# ice40.net
KiCad netlist of a schematic drawn in Altium Designer
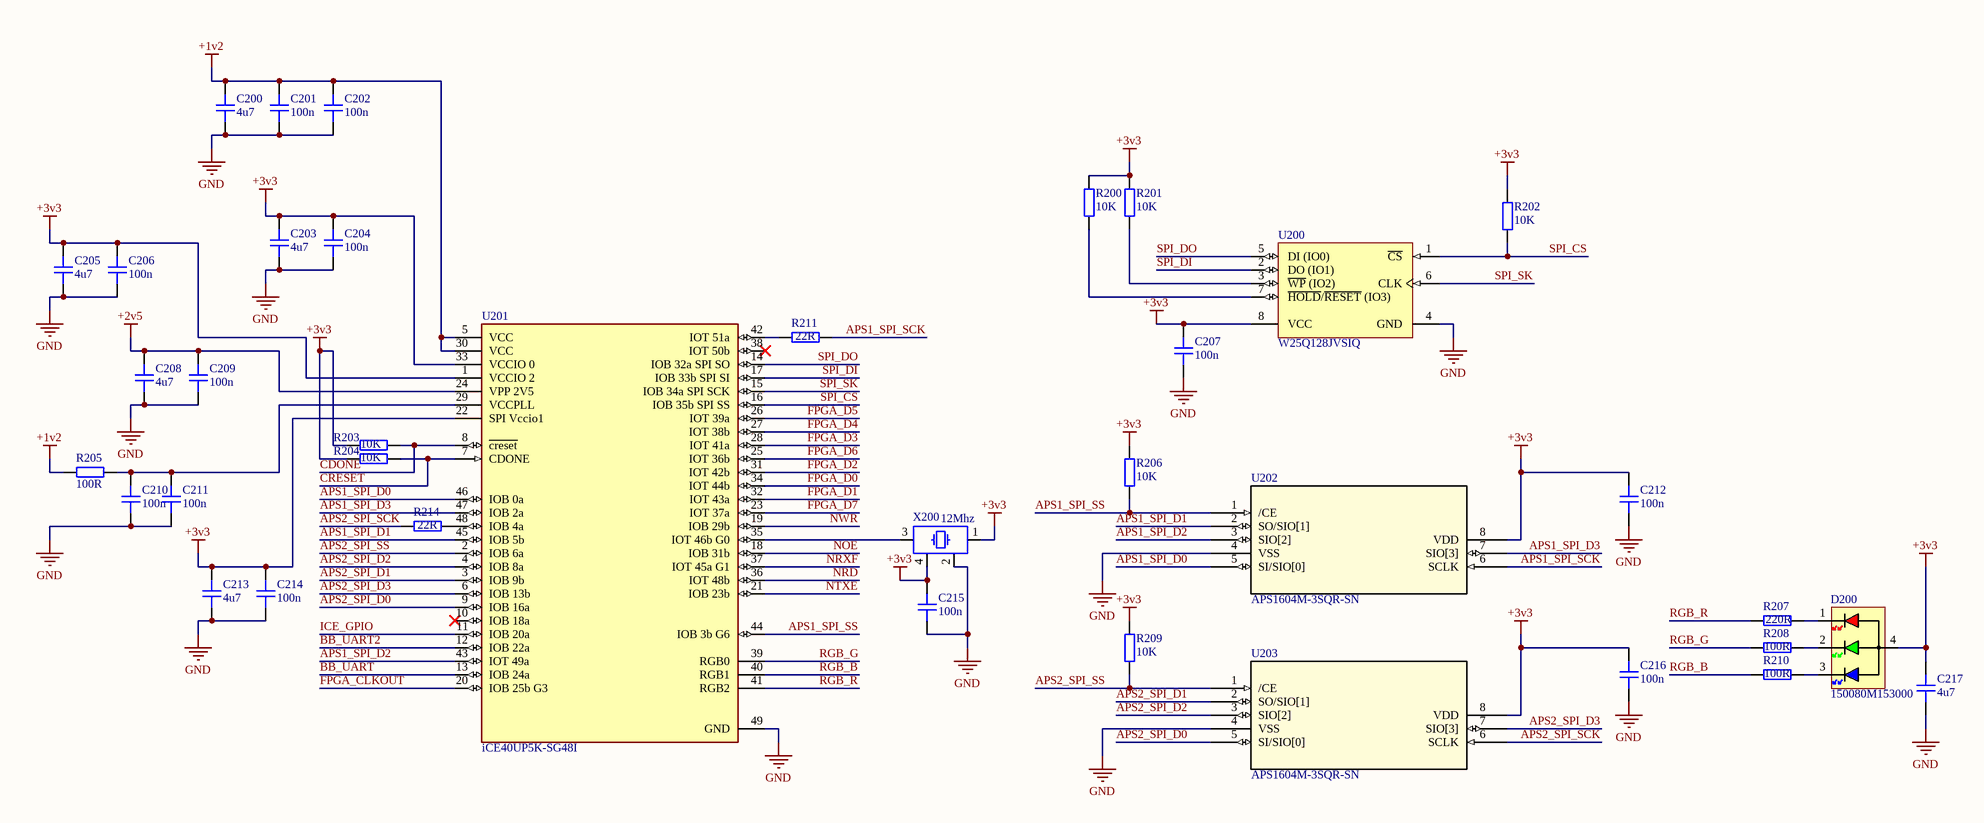
[diagram p0: ice40.SchDoc]

(export (version "E")
  (design (tool "Eeschema 10.0.6"))
  (components
    (comp (ref "C200")
      (value "4u7")
      (footprint "CAP_0402")
      (description "Capacitor SMD 0402")
      (fields (field (name "MANUFACTURER PART NUMBER") "GRM155R61E475ME15D"))
      (libsource (lib "Schematic-Lib-PhilsLab") (part "CAP_0402"))
    )
    (comp (ref "C201")
      (value "100n")
      (footprint "CAP_0402")
      (description "Capacitor SMD 0402")
      (fields (field (name "MANUFACTURER PART NUMBER") "CL05B104KO5NNNC"))
      (libsource (lib "Schematic-Lib-PhilsLab") (part "CAP_0402"))
    )
    (comp (ref "C202")
      (value "100n")
      (footprint "CAP_0402")
      (description "Capacitor SMD 0402")
      (fields (field (name "MANUFACTURER PART NUMBER") "CL05B104KO5NNNC"))
      (libsource (lib "Schematic-Lib-PhilsLab") (part "CAP_0402"))
    )
    (comp (ref "C203")
      (value "4u7")
      (footprint "CAP_0402")
      (description "Capacitor SMD 0402")
      (fields (field (name "MANUFACTURER PART NUMBER") "GRM155R61E475ME15D"))
      (libsource (lib "Schematic-Lib-PhilsLab") (part "CAP_0402"))
    )
    (comp (ref "C204")
      (value "100n")
      (footprint "CAP_0402")
      (description "Capacitor SMD 0402")
      (fields (field (name "MANUFACTURER PART NUMBER") "CL05B104KO5NNNC"))
      (libsource (lib "Schematic-Lib-PhilsLab") (part "CAP_0402"))
    )
    (comp (ref "C205")
      (value "4u7")
      (footprint "CAP_0402")
      (description "Capacitor SMD 0402")
      (fields (field (name "MANUFACTURER PART NUMBER") "GRM155R61E475ME15D"))
      (libsource (lib "Schematic-Lib-PhilsLab") (part "CAP_0402"))
    )
    (comp (ref "C206")
      (value "100n")
      (footprint "CAP_0402")
      (description "Capacitor SMD 0402")
      (fields (field (name "MANUFACTURER PART NUMBER") "CL05B104KO5NNNC"))
      (libsource (lib "Schematic-Lib-PhilsLab") (part "CAP_0402"))
    )
    (comp (ref "C207")
      (value "100n")
      (footprint "CAP_0402")
      (description "Capacitor SMD 0402")
      (fields (field (name "MANUFACTURER PART NUMBER") "CL05B104KO5NNNC"))
      (libsource (lib "Schematic-Lib-PhilsLab") (part "CAP_0402"))
    )
    (comp (ref "C208")
      (value "4u7")
      (footprint "CAP_0402")
      (description "Capacitor SMD 0402")
      (fields (field (name "MANUFACTURER PART NUMBER") "GRM155R61E475ME15D"))
      (libsource (lib "Schematic-Lib-PhilsLab") (part "CAP_0402"))
    )
    (comp (ref "C209")
      (value "100n")
      (footprint "CAP_0402")
      (description "Capacitor SMD 0402")
      (fields (field (name "MANUFACTURER PART NUMBER") "CL05B104KO5NNNC"))
      (libsource (lib "Schematic-Lib-PhilsLab") (part "CAP_0402"))
    )
    (comp (ref "C210")
      (value "100n")
      (footprint "CAP_0402")
      (description "Capacitor SMD 0402")
      (fields (field (name "MANUFACTURER PART NUMBER") "CL05B104KO5NNNC"))
      (libsource (lib "Schematic-Lib-PhilsLab") (part "CAP_0402"))
    )
    (comp (ref "C211")
      (value "100n")
      (footprint "CAP_0402")
      (description "Capacitor SMD 0402")
      (fields (field (name "MANUFACTURER PART NUMBER") "CL05B104KO5NNNC"))
      (libsource (lib "Schematic-Lib-PhilsLab") (part "CAP_0402"))
    )
    (comp (ref "C212")
      (value "100n")
      (footprint "CAP_0402")
      (description "Capacitor SMD 0402")
      (fields (field (name "MANUFACTURER PART NUMBER") "CL05B104KO5NNNC"))
      (libsource (lib "Schematic-Lib-PhilsLab") (part "CAP_0402"))
    )
    (comp (ref "C213")
      (value "4u7")
      (footprint "CAP_0402")
      (description "Capacitor SMD 0402")
      (fields (field (name "MANUFACTURER PART NUMBER") "GRM155R61E475ME15D"))
      (libsource (lib "Schematic-Lib-PhilsLab") (part "CAP_0402"))
    )
    (comp (ref "C214")
      (value "100n")
      (footprint "CAP_0402")
      (description "Capacitor SMD 0402")
      (fields (field (name "MANUFACTURER PART NUMBER") "CL05B104KO5NNNC"))
      (libsource (lib "Schematic-Lib-PhilsLab") (part "CAP_0402"))
    )
    (comp (ref "C215")
      (value "100n")
      (footprint "CAP_0402")
      (description "Capacitor SMD 0402")
      (fields (field (name "MANUFACTURER PART NUMBER") "CL05B104KO5NNNC"))
      (libsource (lib "Schematic-Lib-PhilsLab") (part "CAP_0402"))
    )
    (comp (ref "C216")
      (value "100n")
      (footprint "CAP_0402")
      (description "Capacitor SMD 0402")
      (fields (field (name "MANUFACTURER PART NUMBER") "CL05B104KO5NNNC"))
      (libsource (lib "Schematic-Lib-PhilsLab") (part "CAP_0402"))
    )
    (comp (ref "C217")
      (value "4u7")
      (footprint "CAP_0402")
      (description "Capacitor SMD 0402")
      (fields (field (name "MANUFACTURER PART NUMBER") "GRM155R61E475ME15D"))
      (libsource (lib "Schematic-Lib-PhilsLab") (part "CAP_0402"))
    )
    (comp (ref "D200")
      (value "150080M153000")
      (footprint "150080M153000")
      (description "RGB LED Common Anode SMD Diffused 0805 Top View")
      (fields (field (name "MANUFACTURER") "Wurth"))
      (libsource (lib "Schematic-Lib-PhilsLab") (part "150080M153000"))
    )
    (comp (ref "R200")
      (value "10K")
      (footprint "RES_0402")
      (description "Resistor SMD 0402")
      (fields (field (name "MANUFACTURER PART NUMBER") "0402WGF1002TCE"))
      (libsource (lib "Schematic-Lib-PhilsLab") (part "RES_0402"))
    )
    (comp (ref "R201")
      (value "10K")
      (footprint "RES_0402")
      (description "Resistor SMD 0402")
      (fields (field (name "MANUFACTURER PART NUMBER") "0402WGF1002TCE"))
      (libsource (lib "Schematic-Lib-PhilsLab") (part "RES_0402"))
    )
    (comp (ref "R202")
      (value "10K")
      (footprint "RES_0402")
      (description "Resistor SMD 0402")
      (fields (field (name "MANUFACTURER PART NUMBER") "0402WGF1002TCE"))
      (libsource (lib "Schematic-Lib-PhilsLab") (part "RES_0402"))
    )
    (comp (ref "R203")
      (value "10K")
      (footprint "RES_0402")
      (description "Resistor SMD 0402")
      (fields (field (name "MANUFACTURER PART NUMBER") "0402WGF1002TCE"))
      (libsource (lib "Schematic-Lib-PhilsLab") (part "RES_0402"))
    )
    (comp (ref "R204")
      (value "10K")
      (footprint "RES_0402")
      (description "Resistor SMD 0402")
      (fields (field (name "MANUFACTURER PART NUMBER") "0402WGF1002TCE"))
      (libsource (lib "Schematic-Lib-PhilsLab") (part "RES_0402"))
    )
    (comp (ref "R205")
      (value "100R")
      (footprint "RES_0402")
      (description "Resistor SMD 0402")
      (fields (field (name "MANUFACTURER PART NUMBER") "0402WGF1000TCE"))
      (libsource (lib "Schematic-Lib-PhilsLab") (part "RES_0402"))
    )
    (comp (ref "R206")
      (value "10K")
      (footprint "RES_0402")
      (description "Resistor SMD 0402")
      (fields (field (name "MANUFACTURER PART NUMBER") "0402WGF1002TCE"))
      (libsource (lib "Schematic-Lib-PhilsLab") (part "RES_0402"))
    )
    (comp (ref "R207")
      (value "220R")
      (footprint "RES_0402")
      (description "Resistor SMD 0402")
      (fields (field (name "MANUFACTURER PART NUMBER") "0402WGF2200TCE"))
      (libsource (lib "Schematic-Lib-PhilsLab") (part "RES_0402"))
    )
    (comp (ref "R208")
      (value "100R")
      (footprint "RES_0402")
      (description "Resistor SMD 0402")
      (fields (field (name "MANUFACTURER PART NUMBER") "0402WGF1000TCE"))
      (libsource (lib "Schematic-Lib-PhilsLab") (part "RES_0402"))
    )
    (comp (ref "R209")
      (value "10K")
      (footprint "RES_0402")
      (description "Resistor SMD 0402")
      (fields (field (name "MANUFACTURER PART NUMBER") "0402WGF1002TCE"))
      (libsource (lib "Schematic-Lib-PhilsLab") (part "RES_0402"))
    )
    (comp (ref "R210")
      (value "100R")
      (footprint "RES_0402")
      (description "Resistor SMD 0402")
      (fields (field (name "MANUFACTURER PART NUMBER") "0402WGF1000TCE"))
      (libsource (lib "Schematic-Lib-PhilsLab") (part "RES_0402"))
    )
    (comp (ref "R211")
      (value "22R")
      (footprint "RES_0402")
      (description "Resistor SMD 0402")
      (fields (field (name "MANUFACTURER PART NUMBER") "0402WGF220JTCE"))
      (libsource (lib "Schematic-Lib-PhilsLab") (part "RES_0402"))
    )
    (comp (ref "R214")
      (value "22R")
      (footprint "RES_0402")
      (description "Resistor SMD 0402")
      (fields (field (name "MANUFACTURER PART NUMBER") "0402WGF220JTCE"))
      (libsource (lib "Schematic-Lib-PhilsLab") (part "RES_0402"))
    )
    (comp (ref "U200")
      (value "W25Q128JVSIQ")
      (footprint "WINB-SOIC-8_M")
      (fields (field (name "MANUFACTURER") "Winbond"))
      (libsource (lib "Altium Content Vault") (part "WINB-W25Q128FVSIG-SOIC-8"))
    )
    (comp (ref "U201")
      (value "iCE40UP5K-SG48I")
      (footprint "FP-QFN-48-IPC_C")
      (description "ICE40-ULTRAPLUS, 5280 LUTS, 1.2V")
      (fields
        (field (name "MANUFACTURER") "Lattice")
        (field (name "OCTOPART") "https://octopart.com/ice40up5k-sg48i-lattice+semiconductor-87369311")
      )
      (libsource (lib "Altium Content Vault") (part "90c839ece6b9b86f6dd6a74a4566a88"))
    )
    (comp (ref "U202")
      (value "APS1604M-3SQR-SN")
      (footprint "SOP8L_APS1604M-3SQR-SN_APY")
      (description "No Description Available")
      (libsource (lib "APS1604M-3SQR-SN") (part "APS1604M-3SQR-SN"))
    )
    (comp (ref "U203")
      (value "APS1604M-3SQR-SN")
      (footprint "SOP8L_APS1604M-3SQR-SN_APY")
      (description "No Description Available")
      (libsource (lib "APS1604M-3SQR-SN") (part "APS1604M-3SQR-SN"))
    )
    (comp (ref "X200")
      (value "12Mhz")
      (footprint "XTAL_2520")
      (description "Crystal SMD 2520")
      (fields (field (name "MANUFACTURER PART NUMBER") "SX2M12.000B10F20TNN"))
      (libsource (lib "Schematic-Lib-PhilsLab") (part "XTAL_2520"))
    )
  )
  (nets
    (net (code "1") (name "+1v2") (class "Default")
      (node (ref "C200") (pin "2") (pinfunction "2_2") (pintype "passive"))
      (node (ref "C201") (pin "2") (pinfunction "2_2") (pintype "passive"))
      (node (ref "C202") (pin "2") (pinfunction "2_2") (pintype "passive"))
      (node (ref "R205") (pin "1") (pinfunction "1_1") (pintype "passive"))
      (node (ref "U201") (pin "30") (pinfunction "VCC_30") (pintype "power_in"))
      (node (ref "U201") (pin "5") (pinfunction "VCC_5") (pintype "power_in"))
    )
    (net (code "2") (name "+2v5") (class "Default")
      (node (ref "C208") (pin "2") (pinfunction "2_2") (pintype "passive"))
      (node (ref "C209") (pin "2") (pinfunction "2_2") (pintype "passive"))
      (node (ref "U201") (pin "24") (pinfunction "VPP_2V5_24") (pintype "power_in"))
    )
    (net (code "3") (name "+3v3") (class "Default")
      (node (ref "C203") (pin "2") (pinfunction "2_2") (pintype "passive"))
      (node (ref "C204") (pin "2") (pinfunction "2_2") (pintype "passive"))
      (node (ref "C205") (pin "2") (pinfunction "2_2") (pintype "passive"))
      (node (ref "C206") (pin "2") (pinfunction "2_2") (pintype "passive"))
      (node (ref "C207") (pin "2") (pinfunction "2_2") (pintype "passive"))
      (node (ref "C212") (pin "2") (pinfunction "2_2") (pintype "passive"))
      (node (ref "C213") (pin "2") (pinfunction "2_2") (pintype "passive"))
      (node (ref "C214") (pin "2") (pinfunction "2_2") (pintype "passive"))
      (node (ref "C215") (pin "1") (pinfunction "1_1") (pintype "passive"))
      (node (ref "C216") (pin "2") (pinfunction "2_2") (pintype "passive"))
      (node (ref "C217") (pin "2") (pinfunction "2_2") (pintype "passive"))
      (node (ref "D200") (pin "4") (pinfunction "AC_4") (pintype "passive"))
      (node (ref "R200") (pin "2") (pinfunction "2_2") (pintype "passive"))
      (node (ref "R201") (pin "2") (pinfunction "2_2") (pintype "passive"))
      (node (ref "R202") (pin "2") (pinfunction "2_2") (pintype "passive"))
      (node (ref "R203") (pin "1") (pinfunction "1_1") (pintype "passive"))
      (node (ref "R204") (pin "1") (pinfunction "1_1") (pintype "passive"))
      (node (ref "R206") (pin "2") (pinfunction "2_2") (pintype "passive"))
      (node (ref "R209") (pin "2") (pinfunction "2_2") (pintype "passive"))
      (node (ref "U200") (pin "8") (pinfunction "VCC_8") (pintype "power_in"))
      (node (ref "U201") (pin "1") (pinfunction "VCCIO_2_1") (pintype "power_in"))
      (node (ref "U201") (pin "22") (pinfunction "SPI_Vccio1_22") (pintype "power_in"))
      (node (ref "U201") (pin "33") (pinfunction "VCCIO_0_33") (pintype "power_in"))
      (node (ref "U202") (pin "8") (pinfunction "VDD_8") (pintype "power_in"))
      (node (ref "U203") (pin "8") (pinfunction "VDD_8") (pintype "power_in"))
      (node (ref "X200") (pin "1") (pinfunction "1_1") (pintype "passive"))
      (node (ref "X200") (pin "4") (pinfunction "4_4") (pintype "passive"))
    )
    (net (code "4") (name "/APS1_SPI_D0") (class "Default")
      (node (ref "U201") (pin "46") (pinfunction "IOB_0a_46") (pintype "bidirectional"))
      (node (ref "U202") (pin "5") (pinfunction "SI/SIO[0]_5") (pintype "bidirectional"))
    )
    (net (code "5") (name "/APS1_SPI_D1") (class "Default")
      (node (ref "U201") (pin "45") (pinfunction "IOB_5b_45") (pintype "bidirectional"))
      (node (ref "U202") (pin "2") (pinfunction "SO/SIO[1]_2") (pintype "bidirectional"))
    )
    (net (code "6") (name "/APS1_SPI_D2") (class "Default")
      (node (ref "U201") (pin "43") (pinfunction "IOT_49a_43") (pintype "bidirectional"))
      (node (ref "U202") (pin "3") (pinfunction "SIO[2]_3") (pintype "bidirectional"))
    )
    (net (code "7") (name "/APS1_SPI_D3") (class "Default")
      (node (ref "U201") (pin "47") (pinfunction "IOB_2a_47") (pintype "bidirectional"))
      (node (ref "U202") (pin "7") (pinfunction "SIO[3]_7") (pintype "bidirectional"))
    )
    (net (code "8") (name "/APS1_SPI_SCK") (class "Default")
      (node (ref "R211") (pin "2") (pinfunction "2_2") (pintype "passive"))
      (node (ref "U202") (pin "6") (pinfunction "SCLK_6") (pintype "input"))
    )
    (net (code "9") (name "/APS1_SPI_SS") (class "Default")
      (node (ref "R206") (pin "1") (pinfunction "1_1") (pintype "passive"))
      (node (ref "U201") (pin "44") (pinfunction "IOB_3b_G6_44") (pintype "bidirectional"))
      (node (ref "U202") (pin "1") (pinfunction "/CE_1") (pintype "input"))
    )
    (net (code "10") (name "/APS2_SPI_D0") (class "Default")
      (node (ref "U201") (pin "9") (pinfunction "IOB_16a_9") (pintype "bidirectional"))
      (node (ref "U203") (pin "5") (pinfunction "SI/SIO[0]_5") (pintype "bidirectional"))
    )
    (net (code "11") (name "/APS2_SPI_D1") (class "Default")
      (node (ref "U201") (pin "3") (pinfunction "IOB_9b_3") (pintype "bidirectional"))
      (node (ref "U203") (pin "2") (pinfunction "SO/SIO[1]_2") (pintype "bidirectional"))
    )
    (net (code "12") (name "/APS2_SPI_D2") (class "Default")
      (node (ref "U201") (pin "4") (pinfunction "IOB_8a_4") (pintype "bidirectional"))
      (node (ref "U203") (pin "3") (pinfunction "SIO[2]_3") (pintype "bidirectional"))
    )
    (net (code "13") (name "/APS2_SPI_D3") (class "Default")
      (node (ref "U201") (pin "6") (pinfunction "IOB_13b_6") (pintype "bidirectional"))
      (node (ref "U203") (pin "7") (pinfunction "SIO[3]_7") (pintype "bidirectional"))
    )
    (net (code "14") (name "/APS2_SPI_SCK") (class "Default")
      (node (ref "R214") (pin "1") (pinfunction "1_1") (pintype "passive"))
      (node (ref "U203") (pin "6") (pinfunction "SCLK_6") (pintype "input"))
    )
    (net (code "15") (name "/APS2_SPI_SS") (class "Default")
      (node (ref "R209") (pin "1") (pinfunction "1_1") (pintype "passive"))
      (node (ref "U201") (pin "2") (pinfunction "IOB_6a_2") (pintype "bidirectional"))
      (node (ref "U203") (pin "1") (pinfunction "/CE_1") (pintype "input"))
    )
    (net (code "16") (name "/BB_UART") (class "Default")
      (node (ref "U201") (pin "13") (pinfunction "IOB_24a_13") (pintype "bidirectional"))
    )
    (net (code "17") (name "/BB_UART2") (class "Default")
      (node (ref "U201") (pin "12") (pinfunction "IOB_22a_12") (pintype "bidirectional"))
    )
    (net (code "18") (name "/CDONE") (class "Default")
      (node (ref "R203") (pin "2") (pinfunction "2_2") (pintype "passive"))
      (node (ref "U201") (pin "8") (pinfunction "~{creset}_8") (pintype "bidirectional"))
    )
    (net (code "19") (name "/CRESET") (class "Default")
      (node (ref "R204") (pin "2") (pinfunction "2_2") (pintype "passive"))
      (node (ref "U201") (pin "7") (pinfunction "CDONE_7") (pintype "input"))
    )
    (net (code "20") (name "/FPGA_CLKOUT") (class "Default")
      (node (ref "U201") (pin "20") (pinfunction "IOB_25b_G3_20") (pintype "bidirectional"))
    )
    (net (code "21") (name "/FPGA_D0") (class "Default")
      (node (ref "U201") (pin "34") (pinfunction "IOT_44b_34") (pintype "bidirectional"))
    )
    (net (code "22") (name "/FPGA_D1") (class "Default")
      (node (ref "U201") (pin "32") (pinfunction "IOT_43a_32") (pintype "bidirectional"))
    )
    (net (code "23") (name "/FPGA_D2") (class "Default")
      (node (ref "U201") (pin "31") (pinfunction "IOT_42b_31") (pintype "bidirectional"))
    )
    (net (code "24") (name "/FPGA_D3") (class "Default")
      (node (ref "U201") (pin "28") (pinfunction "IOT_41a_28") (pintype "bidirectional"))
    )
    (net (code "25") (name "/FPGA_D4") (class "Default")
      (node (ref "U201") (pin "27") (pinfunction "IOT_38b_27") (pintype "bidirectional"))
    )
    (net (code "26") (name "/FPGA_D5") (class "Default")
      (node (ref "U201") (pin "26") (pinfunction "IOT_39a_26") (pintype "bidirectional"))
    )
    (net (code "27") (name "/FPGA_D6") (class "Default")
      (node (ref "U201") (pin "25") (pinfunction "IOT_36b_25") (pintype "bidirectional"))
    )
    (net (code "28") (name "/FPGA_D7") (class "Default")
      (node (ref "U201") (pin "23") (pinfunction "IOT_37a_23") (pintype "bidirectional"))
    )
    (net (code "29") (name "/ICE_GPIO") (class "Default")
      (node (ref "U201") (pin "11") (pinfunction "IOB_20a_11") (pintype "bidirectional"))
    )
    (net (code "30") (name "/NOE") (class "Default")
      (node (ref "U201") (pin "18") (pinfunction "IOB_31b_18") (pintype "bidirectional"))
    )
    (net (code "31") (name "/NRD") (class "Default")
      (node (ref "U201") (pin "36") (pinfunction "IOT_48b_36") (pintype "bidirectional"))
    )
    (net (code "32") (name "/NRXF") (class "Default")
      (node (ref "U201") (pin "37") (pinfunction "IOT_45a_G1_37") (pintype "bidirectional"))
    )
    (net (code "33") (name "/NTXE") (class "Default")
      (node (ref "U201") (pin "21") (pinfunction "IOB_23b_21") (pintype "bidirectional"))
    )
    (net (code "34") (name "/NWR") (class "Default")
      (node (ref "U201") (pin "19") (pinfunction "IOB_29b_19") (pintype "bidirectional"))
    )
    (net (code "35") (name "/RGB_B") (class "Default")
      (node (ref "R210") (pin "1") (pinfunction "1_1") (pintype "passive"))
      (node (ref "U201") (pin "40") (pinfunction "RGB1_40") (pintype "open_collector"))
    )
    (net (code "36") (name "/RGB_G") (class "Default")
      (node (ref "R208") (pin "1") (pinfunction "1_1") (pintype "passive"))
      (node (ref "U201") (pin "39") (pinfunction "RGB0_39") (pintype "open_collector"))
    )
    (net (code "37") (name "/RGB_R") (class "Default")
      (node (ref "R207") (pin "1") (pinfunction "1_1") (pintype "passive"))
      (node (ref "U201") (pin "41") (pinfunction "RGB2_41") (pintype "open_collector"))
    )
    (net (code "38") (name "/SPI_CS") (class "Default")
      (node (ref "R202") (pin "1") (pinfunction "1_1") (pintype "passive"))
      (node (ref "U200") (pin "1") (pinfunction "~{CS}_1") (pintype "input"))
      (node (ref "U201") (pin "16") (pinfunction "IOB_35b_SPI_SS_16") (pintype "bidirectional"))
    )
    (net (code "39") (name "/SPI_DI") (class "Default")
      (node (ref "U200") (pin "2") (pinfunction "DO_(IO1)_2") (pintype "bidirectional"))
      (node (ref "U201") (pin "17") (pinfunction "IOB_33b_SPI_SI_17") (pintype "bidirectional"))
    )
    (net (code "40") (name "/SPI_DO") (class "Default")
      (node (ref "U200") (pin "5") (pinfunction "DI_(IO0)_5") (pintype "bidirectional"))
      (node (ref "U201") (pin "14") (pinfunction "IOB_32a_SPI_SO_14") (pintype "bidirectional"))
    )
    (net (code "41") (name "/SPI_SK") (class "Default")
      (node (ref "U200") (pin "6") (pinfunction "CLK_6") (pintype "input"))
      (node (ref "U201") (pin "15") (pinfunction "IOB_34a_SPI_SCK_15") (pintype "bidirectional"))
    )
    (net (code "42") (name "GND") (class "Default")
      (node (ref "C200") (pin "1") (pinfunction "1_1") (pintype "passive"))
      (node (ref "C201") (pin "1") (pinfunction "1_1") (pintype "passive"))
      (node (ref "C202") (pin "1") (pinfunction "1_1") (pintype "passive"))
      (node (ref "C203") (pin "1") (pinfunction "1_1") (pintype "passive"))
      (node (ref "C204") (pin "1") (pinfunction "1_1") (pintype "passive"))
      (node (ref "C205") (pin "1") (pinfunction "1_1") (pintype "passive"))
      (node (ref "C206") (pin "1") (pinfunction "1_1") (pintype "passive"))
      (node (ref "C207") (pin "1") (pinfunction "1_1") (pintype "passive"))
      (node (ref "C208") (pin "1") (pinfunction "1_1") (pintype "passive"))
      (node (ref "C209") (pin "1") (pinfunction "1_1") (pintype "passive"))
      (node (ref "C210") (pin "1") (pinfunction "1_1") (pintype "passive"))
      (node (ref "C211") (pin "1") (pinfunction "1_1") (pintype "passive"))
      (node (ref "C212") (pin "1") (pinfunction "1_1") (pintype "passive"))
      (node (ref "C213") (pin "1") (pinfunction "1_1") (pintype "passive"))
      (node (ref "C214") (pin "1") (pinfunction "1_1") (pintype "passive"))
      (node (ref "C215") (pin "2") (pinfunction "2_2") (pintype "passive"))
      (node (ref "C216") (pin "1") (pinfunction "1_1") (pintype "passive"))
      (node (ref "C217") (pin "1") (pinfunction "1_1") (pintype "passive"))
      (node (ref "U200") (pin "4") (pinfunction "GND_4") (pintype "power_in"))
      (node (ref "U201") (pin "49") (pinfunction "GND_49") (pintype "power_in"))
      (node (ref "U202") (pin "4") (pinfunction "VSS_4") (pintype "power_in"))
      (node (ref "U203") (pin "4") (pinfunction "VSS_4") (pintype "power_in"))
      (node (ref "X200") (pin "2") (pinfunction "2_2") (pintype "passive"))
    )
    (net (code "43") (name "Net-(D200-CB)") (class "Default")
      (node (ref "D200") (pin "3") (pinfunction "CB_3") (pintype "passive"))
      (node (ref "R210") (pin "2") (pinfunction "2_2") (pintype "passive"))
    )
    (net (code "44") (name "Net-(D200-CG)") (class "Default")
      (node (ref "D200") (pin "2") (pinfunction "CG_2") (pintype "passive"))
      (node (ref "R208") (pin "2") (pinfunction "2_2") (pintype "passive"))
    )
    (net (code "45") (name "Net-(D200-CR)") (class "Default")
      (node (ref "D200") (pin "1") (pinfunction "CR_1") (pintype "passive"))
      (node (ref "R207") (pin "2") (pinfunction "2_2") (pintype "passive"))
    )
    (net (code "46") (name "Net-(U200-~{HOLD}{slash}~{RESET}_(IO3))") (class "Default")
      (node (ref "R200") (pin "1") (pinfunction "1_1") (pintype "passive"))
      (node (ref "U200") (pin "7") (pinfunction "~{HOLD}/~{RESET}_(IO3)_7") (pintype "bidirectional"))
    )
    (net (code "47") (name "Net-(U200-~{WP}_(IO2))") (class "Default")
      (node (ref "R201") (pin "1") (pinfunction "1_1") (pintype "passive"))
      (node (ref "U200") (pin "3") (pinfunction "~{WP}_(IO2)_3") (pintype "bidirectional"))
    )
    (net (code "48") (name "Net-(U201-IOB_4a)") (class "Default")
      (node (ref "R214") (pin "2") (pinfunction "2_2") (pintype "passive"))
      (node (ref "U201") (pin "48") (pinfunction "IOB_4a_48") (pintype "bidirectional"))
    )
    (net (code "49") (name "Net-(U201-IOT_46b_G0)") (class "Default")
      (node (ref "U201") (pin "35") (pinfunction "IOT_46b_G0_35") (pintype "bidirectional"))
      (node (ref "X200") (pin "3") (pinfunction "3_3") (pintype "passive"))
    )
    (net (code "50") (name "Net-(U201-IOT_51a)") (class "Default")
      (node (ref "R211") (pin "1") (pinfunction "1_1") (pintype "passive"))
      (node (ref "U201") (pin "42") (pinfunction "IOT_51a_42") (pintype "bidirectional"))
    )
    (net (code "51") (name "Net-(U201-VCCPLL)") (class "Default")
      (node (ref "C210") (pin "2") (pinfunction "2_2") (pintype "passive"))
      (node (ref "C211") (pin "2") (pinfunction "2_2") (pintype "passive"))
      (node (ref "R205") (pin "2") (pinfunction "2_2") (pintype "passive"))
      (node (ref "U201") (pin "29") (pinfunction "VCCPLL_29") (pintype "power_in"))
    )
    (net (code "52") (name "unconnected-(U201-IOB_18a-Pad10)") (class "Default")
      (node (ref "U201") (pin "10") (pinfunction "IOB_18a_10") (pintype "bidirectional+no_connect"))
    )
    (net (code "53") (name "unconnected-(U201-IOT_50b-Pad38)") (class "Default")
      (node (ref "U201") (pin "38") (pinfunction "IOT_50b_38") (pintype "bidirectional+no_connect"))
    )
  )
)
